# StrobeV2.net
KiCad netlist of a schematic drawn in EAGLE
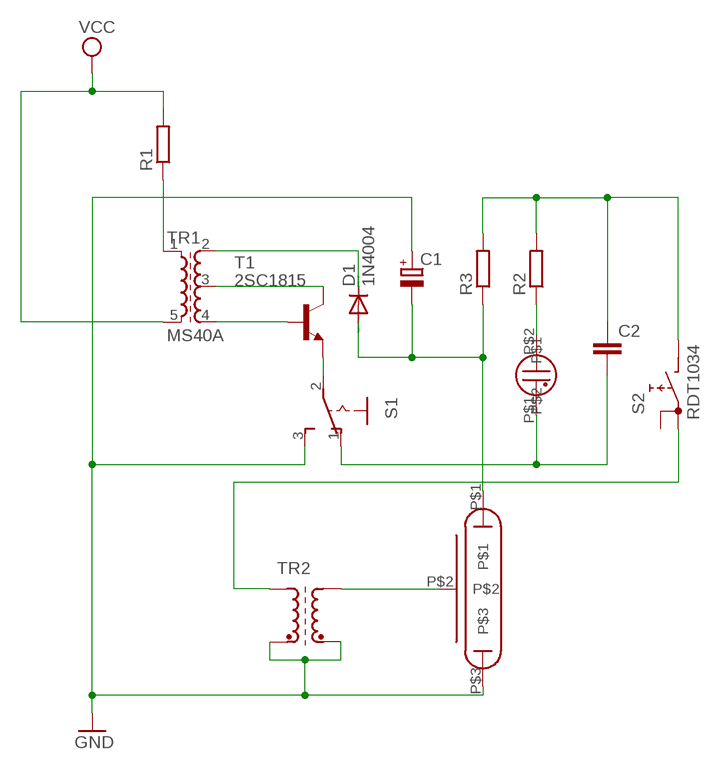
[diagram p0: schematic, sheet 1]

(export (version "E")
  (design (tool "Eeschema 10.0.6"))
  (components
    (comp (ref "C1")
      (value "CPOL-EU140CLH-0810")
      (footprint "eagle-import:140CLH-0810")
      (libsource (lib "eagle-import") (part "CPOL-EU140CLH-0810"))
    )
    (comp (ref "C2")
      (value "C-EU150-054X183")
      (footprint "eagle-import:C150-054X183")
      (libsource (lib "eagle-import") (part "C-EU150-054X183"))
    )
    (comp (ref "D1")
      (value "1N4004")
      (footprint "eagle-import:DO41-10")
      (libsource (lib "eagle-import") (part "1N4004"))
    )
    (comp (ref "R1")
      (value "R-EU_0204/2V")
      (footprint "eagle-import:0204V")
      (libsource (lib "eagle-import") (part "R-EU_0204/2V"))
    )
    (comp (ref "R2")
      (value "R-EU_0204/2V")
      (footprint "eagle-import:0204V")
      (libsource (lib "eagle-import") (part "R-EU_0204/2V"))
    )
    (comp (ref "R3")
      (value "R-EU_0204/2V")
      (footprint "eagle-import:0204V")
      (libsource (lib "eagle-import") (part "R-EU_0204/2V"))
    )
    (comp (ref "S1")
      (value "255SB")
      (footprint "eagle-import:255SB")
      (libsource (lib "eagle-import") (part "255SB"))
    )
    (comp (ref "S2")
      (value "RDT1034")
      (footprint "eagle-import:RDT1034")
      (libsource (lib "eagle-import") (part "RDT1034"))
    )
    (comp (ref "T1")
      (value "2SC1815")
      (footprint "eagle-import:TO92-ECB")
      (libsource (lib "eagle-import") (part "2SC1815"))
    )
    (comp (ref "TR1")
      (value "MS40A")
      (footprint "eagle-import:MS40")
      (libsource (lib "eagle-import") (part "MS40A"))
    )
    (comp (ref "TR2")
      (value "SM-T4")
      (footprint "eagle-import:SM-T4")
      (libsource (lib "eagle-import") (part "SM-T4"))
    )
    (comp (ref "U$1")
      (value "XENON")
      (footprint "eagle-import:XENON")
      (libsource (lib "eagle-import") (part "XENON"))
    )
    (comp (ref "U$2")
      (value "NEON")
      (footprint "eagle-import:NEON")
      (libsource (lib "eagle-import") (part "NEON"))
    )
  )
  (nets
    (net (code "1") (name "GND") (class "Default")
      (node (ref "C1") (pin "+") (pinfunction "+_+") (pintype "passive"))
      (node (ref "S1") (pin "3") (pinfunction "S_3") (pintype "passive"))
      (node (ref "TR2") (pin "2") (pinfunction "E1_2") (pintype "passive"))
      (node (ref "TR2") (pin "4") (pinfunction "E2_4") (pintype "passive"))
      (node (ref "U$1") (pin "P$3") (pinfunction "P$3_P$3") (pintype "bidirectional"))
    )
    (net (code "2") (name "Net-(C1-Pad-)") (class "Default")
      (node (ref "C1") (pin "-") (pinfunction "-_-") (pintype "passive"))
      (node (ref "D1") (pin "A") (pinfunction "A_A") (pintype "passive"))
      (node (ref "R3") (pin "1") (pinfunction "1_1") (pintype "passive"))
      (node (ref "U$1") (pin "P$1") (pinfunction "P$1_P$1") (pintype "bidirectional"))
    )
    (net (code "3") (name "Net-(C2-Pad1)") (class "Default")
      (node (ref "C2") (pin "1") (pinfunction "1_1") (pintype "passive"))
      (node (ref "R2") (pin "2") (pinfunction "2_2") (pintype "passive"))
      (node (ref "R3") (pin "2") (pinfunction "2_2") (pintype "passive"))
      (node (ref "S2") (pin "B") (pinfunction "B_B") (pintype "passive"))
    )
    (net (code "4") (name "Net-(D1-PadC)") (class "Default")
      (node (ref "D1") (pin "C") (pinfunction "C_C") (pintype "passive"))
      (node (ref "TR1") (pin "2") (pinfunction "2_2") (pintype "passive"))
    )
    (net (code "5") (name "Net-(R1-Pad1)") (class "Default")
      (node (ref "R1") (pin "1") (pinfunction "1_1") (pintype "passive"))
      (node (ref "TR1") (pin "1") (pinfunction "1_1") (pintype "passive"))
    )
    (net (code "6") (name "Net-(R2-Pad1)") (class "Default")
      (node (ref "R2") (pin "1") (pinfunction "1_1") (pintype "passive"))
      (node (ref "U$2") (pin "P$2") (pinfunction "P$2_P$2") (pintype "bidirectional"))
    )
    (net (code "7") (name "Net-(S1-O)") (class "Default")
      (node (ref "C2") (pin "2") (pinfunction "2_2") (pintype "passive"))
      (node (ref "S1") (pin "1") (pinfunction "O_1") (pintype "passive"))
      (node (ref "U$2") (pin "P$1") (pinfunction "P$1_P$1") (pintype "bidirectional"))
    )
    (net (code "8") (name "Net-(S1-P)") (class "Default")
      (node (ref "S1") (pin "2") (pinfunction "P_2") (pintype "passive"))
      (node (ref "T1") (pin "E") (pinfunction "E_E") (pintype "passive"))
    )
    (net (code "9") (name "Net-(T1-PadB)") (class "Default")
      (node (ref "T1") (pin "B") (pinfunction "B_B") (pintype "passive"))
      (node (ref "TR1") (pin "4") (pinfunction "4_4") (pintype "passive"))
    )
    (net (code "10") (name "Net-(T1-PadC)") (class "Default")
      (node (ref "T1") (pin "C") (pinfunction "C_C") (pintype "passive"))
      (node (ref "TR1") (pin "3") (pinfunction "3_3") (pintype "passive"))
    )
    (net (code "11") (name "Net-(TR2-A1)") (class "Default")
      (node (ref "S2") (pin "A1") (pinfunction "A1_A1") (pintype "passive"))
      (node (ref "TR2") (pin "1") (pinfunction "A1_1") (pintype "passive"))
    )
    (net (code "12") (name "Net-(TR2-A2)") (class "Default")
      (node (ref "TR2") (pin "5") (pinfunction "A2_5") (pintype "passive"))
      (node (ref "U$1") (pin "P$2") (pinfunction "P$2_P$2") (pintype "bidirectional"))
    )
    (net (code "13") (name "VCC") (class "Default")
      (node (ref "R1") (pin "2") (pinfunction "2_2") (pintype "passive"))
      (node (ref "TR1") (pin "5") (pinfunction "5_5") (pintype "passive"))
    )
    (net (code "14") (name "unconnected-(S2-PadA)") (class "Default")
      (node (ref "S2") (pin "A") (pinfunction "A_A") (pintype "passive"))
    )
  )
)
